# Master.net
KiCad netlist of a schematic drawn in Altium Designer
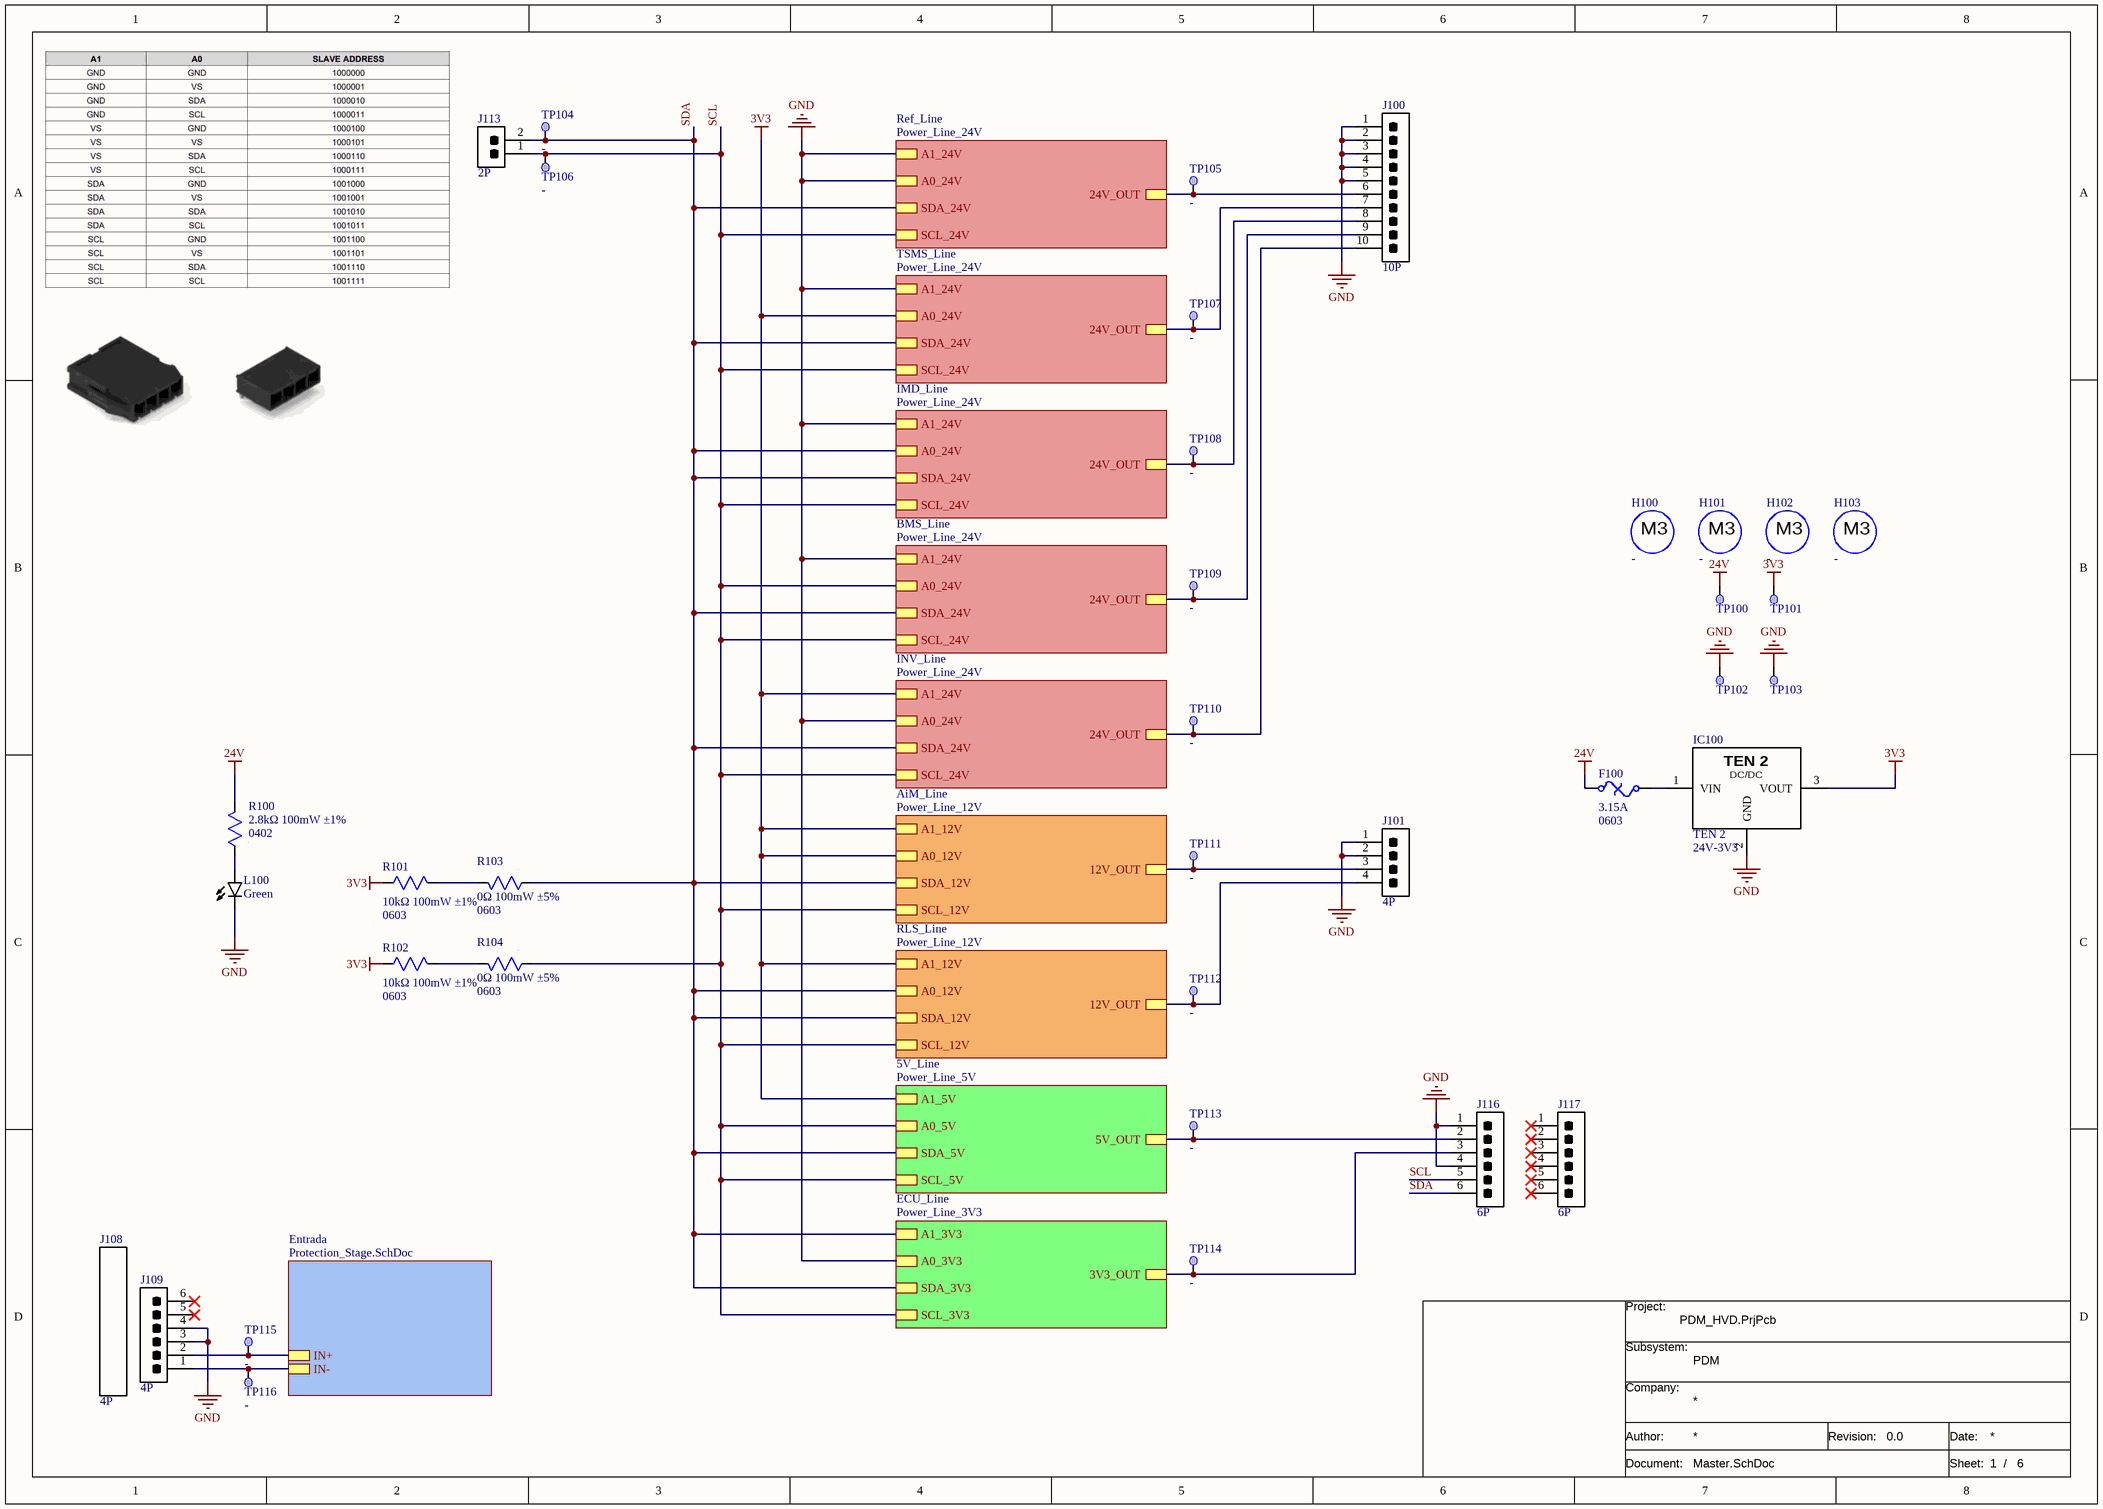
[diagram p0: Master.SchDoc]

(export (version "E")
  (design (tool "Eeschema 10.0.6"))
  (components
    (comp (ref "F100")
      (value "3.15A")
      (footprint "FUSE SMD 0603")
      (description "Surface Mount Fuses 3.15A Slow Blow 0603 SinglFuse")
      (fields
        (field (name "PACKAGE") "0603")
        (field (name "MPN") "SF-0603S315-2")
        (field (name "MANUFACTURER") "Bourns")
      )
      (libsource (lib "eUSR_Database") (part "FUSE"))
    )
    (comp (ref "H100")
      (value "-")
      (footprint "M3")
      (description "M3 Screw")
      (fields (field (name "Comment") "SCREW M3"))
      (libsource (lib "eUSR_Database") (part "SCREW M3"))
    )
    (comp (ref "H101")
      (value "-")
      (footprint "M3")
      (description "M3 Screw")
      (fields (field (name "Comment") "SCREW M3"))
      (libsource (lib "eUSR_Database") (part "SCREW M3"))
    )
    (comp (ref "H102")
      (value "-")
      (footprint "M3")
      (description "M3 Screw")
      (fields (field (name "Comment") "SCREW M3"))
      (libsource (lib "eUSR_Database") (part "SCREW M3"))
    )
    (comp (ref "H103")
      (value "-")
      (footprint "M3")
      (description "M3 Screw")
      (fields (field (name "Comment") "SCREW M3"))
      (libsource (lib "eUSR_Database") (part "SCREW M3"))
    )
    (comp (ref "IC100")
      (value "TEN 2")
      (footprint "TEN 2")
      (description "Convertidores DC/DC para montaje pasante 4.75-36Vin 3.3V 2A switching regulator")
      (fields
        (field (name "ALTIUM_VALUE") "24V-3V3")
        (field (name "MPN") "TSR 2-2433")
        (field (name "MANUFACTURER") "TRACO Power")
      )
      (libsource (lib "eUSR_Database") (part "TEN 2"))
    )
    (comp (ref "J100")
      (value "10P")
      (footprint "657010240101")
      (fields
        (field (name "MPN") "657010240101")
        (field (name "MANUFACTURER") "Wurth Elektronik")
        (field (name "Comment") "CONN 10P")
      )
      (libsource (lib "eUSR_Database") (part "CONN 10P"))
    )
    (comp (ref "J101")
      (value "4P")
      (footprint "657004240101")
      (fields
        (field (name "MPN") "657004240101")
        (field (name "MANUFACTURER") "Wurth Elektronik")
        (field (name "Comment") "CONN 4P")
      )
      (libsource (lib "eUSR_Database") (part "CONN 4P"))
    )
    (comp (ref "J108")
      (value "4P")
      (footprint "657004150201")
      (description "Receptacle Single Row")
      (fields (field (name "MPN") "657004150201") (field (name "MANUFACTURER") "Wurth Elektronik"))
      (libsource (lib "eUSR_Database") (part "AEREO"))
    )
    (comp (ref "J109")
      (value "4P")
      (footprint "657004140101")
      (description "WR-MPC5 Male Header Single Row")
      (fields (field (name "MPN") "657004140101") (field (name "MANUFACTURER") "Wurth Elektronik"))
      (libsource (lib "") (part "CONN 6P_1"))
    )
    (comp (ref "J113")
      (value "2P")
      (footprint "PIN_HEADER_THT_2P")
      (description "Alojamientos de cables y cabecera 2.54MM HIGH TEMP PCB HDR STRIP")
      (fields (field (name "MPN") "HTSW-102-07-G-S") (field (name "MANUFACTURER") "Samtec"))
      (libsource (lib "eUSR_Database") (part "CONN 2P"))
    )
    (comp (ref "J116")
      (value "6P")
      (footprint "HEADERS_MALE_6P_2.54MM")
      (description "Pin Header 6 Position 2.54mm Pitch Single Row Through Hole -55℃~+105℃")
      (fields (field (name "MPN") "2541WV-06P") (field (name "MANUFACTURER") "HanElectricity"))
      (libsource (lib "eUSR_Database") (part "CONN 6P"))
    )
    (comp (ref "J117")
      (value "6P")
      (footprint "HEADERS_MALE_6P_2.54MM")
      (description "Pin Header 6 Position 2.54mm Pitch Single Row Through Hole -55℃~+105℃")
      (fields (field (name "MPN") "2541WV-06P") (field (name "MANUFACTURER") "HanElectricity"))
      (libsource (lib "eUSR_Database") (part "CONN 6P"))
    )
    (comp (ref "L100")
      (value "Green")
      (footprint "LED SMD 0603")
      (description "LED de un solo color Green 525nm 1400mcd 2.85V 73deg 0603")
      (fields (field (name "MPN") "VLMTG1400-GS08") (field (name "MANUFACTURER") "Vishay Semiconductors"))
      (libsource (lib "eUSR_Database") (part "LED WHITE"))
    )
    (comp (ref "R100")
      (value "2.8kΩ 100mW ±1%")
      (footprint "RES SMD 0402")
      (description "Resistores de película gruesa - SMD WRIS-RSKS 28 kOhms 1 % 0.1 W 0402 AEC-Q200")
      (fields
        (field (name "PACKAGE") "0402")
        (field (name "MPN") "560112110228")
        (field (name "MANUFACTURER") "Wurth Elektronik")
      )
      (libsource (lib "eUSR_Database") (part "RES"))
    )
    (comp (ref "R101")
      (value "10kΩ 100mW ±1%")
      (footprint "RES SMD 0603")
      (description "Resistores de película gruesa - SMD WRIS-RSKS 10 kOhms 1 % 0.1 W 0603 AEC-Q200")
      (fields
        (field (name "PACKAGE") "0603")
        (field (name "MPN") "560112116005")
        (field (name "MANUFACTURER") "Wurth Elektronik")
      )
      (libsource (lib "eUSR_Database") (part "RES"))
    )
    (comp (ref "R102")
      (value "10kΩ 100mW ±1%")
      (footprint "RES SMD 0603")
      (description "Resistores de película gruesa - SMD WRIS-RSKS 10 kOhms 1 % 0.1 W 0603 AEC-Q200")
      (fields
        (field (name "PACKAGE") "0603")
        (field (name "MPN") "560112116005")
        (field (name "MANUFACTURER") "Wurth Elektronik")
      )
      (libsource (lib "eUSR_Database") (part "RES"))
    )
    (comp (ref "R103")
      (value "0Ω 100mW ±5%")
      (footprint "RES SMD 0603")
      (description "Resistores de película gruesa - SMD WRIS-RSKS <0.05 Ohms 0.1 W Jumper 0603 AEC-Q200")
      (fields
        (field (name "PACKAGE") "0603")
        (field (name "MPN") "560112116001")
        (field (name "MANUFACTURER") "Wurth Elektronik")
      )
      (libsource (lib "eUSR_Database") (part "RES"))
    )
    (comp (ref "R104")
      (value "0Ω 100mW ±5%")
      (footprint "RES SMD 0603")
      (description "Resistores de película gruesa - SMD WRIS-RSKS <0.05 Ohms 0.1 W Jumper 0603 AEC-Q200")
      (fields
        (field (name "PACKAGE") "0603")
        (field (name "MPN") "560112116001")
        (field (name "MANUFACTURER") "Wurth Elektronik")
      )
      (libsource (lib "eUSR_Database") (part "RES"))
    )
    (comp (ref "TP100")
      (value "Test Point")
      (footprint "TP_THT_1.5MM")
      (description "Test Point 1.5mm THT")
      (libsource (lib "eUSR_Database") (part "TP"))
    )
    (comp (ref "TP101")
      (value "Test Point")
      (footprint "TP_THT_1.5MM")
      (description "Test Point 1.5mm THT")
      (libsource (lib "eUSR_Database") (part "TP"))
    )
    (comp (ref "TP102")
      (value "Test Point")
      (footprint "TP_THT_1.5MM")
      (description "Test Point 1.5mm THT")
      (libsource (lib "eUSR_Database") (part "TP"))
    )
    (comp (ref "TP103")
      (value "Test Point")
      (footprint "TP_THT_1.5MM")
      (description "Test Point 1.5mm THT")
      (libsource (lib "eUSR_Database") (part "TP"))
    )
    (comp (ref "TP104")
      (value "-")
      (footprint "TP_SMD_1MM")
      (description "Test Point")
      (libsource (lib "eUSR_Database") (part "TP1mm"))
    )
    (comp (ref "TP105")
      (value "-")
      (footprint "TP_SMD_1MM")
      (description "Test Point")
      (libsource (lib "eUSR_Database") (part "TP1mm"))
    )
    (comp (ref "TP106")
      (value "-")
      (footprint "TP_SMD_1MM")
      (description "Test Point")
      (libsource (lib "") (part "TP1mm_1"))
    )
    (comp (ref "TP107")
      (value "-")
      (footprint "TP_SMD_1MM")
      (description "Test Point")
      (libsource (lib "eUSR_Database") (part "TP1mm"))
    )
    (comp (ref "TP108")
      (value "-")
      (footprint "TP_SMD_1MM")
      (description "Test Point")
      (libsource (lib "eUSR_Database") (part "TP1mm"))
    )
    (comp (ref "TP109")
      (value "-")
      (footprint "TP_SMD_1MM")
      (description "Test Point")
      (libsource (lib "eUSR_Database") (part "TP1mm"))
    )
    (comp (ref "TP110")
      (value "-")
      (footprint "TP_SMD_1MM")
      (description "Test Point")
      (libsource (lib "eUSR_Database") (part "TP1mm"))
    )
    (comp (ref "TP111")
      (value "-")
      (footprint "TP_SMD_1MM")
      (description "Test Point")
      (libsource (lib "eUSR_Database") (part "TP1mm"))
    )
    (comp (ref "TP112")
      (value "-")
      (footprint "TP_SMD_1MM")
      (description "Test Point")
      (libsource (lib "eUSR_Database") (part "TP1mm"))
    )
    (comp (ref "TP113")
      (value "-")
      (footprint "TP_SMD_1MM")
      (description "Test Point")
      (libsource (lib "eUSR_Database") (part "TP1mm"))
    )
    (comp (ref "TP114")
      (value "-")
      (footprint "TP_SMD_1MM")
      (description "Test Point")
      (libsource (lib "eUSR_Database") (part "TP1mm"))
    )
    (comp (ref "TP115")
      (value "-")
      (footprint "TP_SMD_1MM")
      (description "Test Point")
      (libsource (lib "eUSR_Database") (part "TP1mm"))
    )
    (comp (ref "TP116")
      (value "-")
      (footprint "TP_SMD_1MM")
      (description "Test Point")
      (libsource (lib "") (part "TP1mm_1"))
    )
  )
  (nets
    (net (code "1") (name "/3V3_OUT") (class "Default")
      (node (ref "J116") (pin "3") (pinfunction "3_3") (pintype "passive"))
      (node (ref "TP114") (pin "1") (pinfunction "1_1") (pintype "passive"))
    )
    (net (code "2") (name "/5V_OUT") (class "Default")
      (node (ref "J116") (pin "2") (pinfunction "2_2") (pintype "passive"))
      (node (ref "TP113") (pin "1") (pinfunction "1_1") (pintype "passive"))
    )
    (net (code "3") (name "/12V_OUT") (class "Default")
      (node (ref "J101") (pin "4") (pinfunction "4_4") (pintype "passive"))
      (node (ref "TP112") (pin "1") (pinfunction "1_1") (pintype "passive"))
    )
    (net (code "4") (name "/12V_OUT_1") (class "Default")
      (node (ref "J101") (pin "3") (pinfunction "3_3") (pintype "passive"))
      (node (ref "TP111") (pin "1") (pinfunction "1_1") (pintype "passive"))
    )
    (net (code "5") (name "/24V_OUT") (class "Default")
      (node (ref "J100") (pin "10") (pinfunction "10_10") (pintype "passive"))
      (node (ref "TP110") (pin "1") (pinfunction "1_1") (pintype "passive"))
    )
    (net (code "6") (name "/24V_OUT_1") (class "Default")
      (node (ref "J100") (pin "6") (pinfunction "6_6") (pintype "passive"))
      (node (ref "TP105") (pin "1") (pinfunction "1_1") (pintype "passive"))
    )
    (net (code "7") (name "/24V_OUT_2") (class "Default")
      (node (ref "J100") (pin "7") (pinfunction "7_7") (pintype "passive"))
      (node (ref "TP107") (pin "1") (pinfunction "1_1") (pintype "passive"))
    )
    (net (code "8") (name "/24V_OUT_3") (class "Default")
      (node (ref "J100") (pin "8") (pinfunction "8_8") (pintype "passive"))
      (node (ref "TP108") (pin "1") (pinfunction "1_1") (pintype "passive"))
    )
    (net (code "9") (name "/24V_OUT_4") (class "Default")
      (node (ref "J100") (pin "9") (pinfunction "9_9") (pintype "passive"))
      (node (ref "TP109") (pin "1") (pinfunction "1_1") (pintype "passive"))
    )
    (net (code "10") (name "/IN+") (class "Default")
      (node (ref "J109") (pin "2") (pinfunction "2_2") (pintype "passive"))
      (node (ref "TP115") (pin "1") (pinfunction "1_1") (pintype "passive"))
    )
    (net (code "11") (name "/IN-") (class "Default")
      (node (ref "J109") (pin "1") (pinfunction "1_1") (pintype "passive"))
      (node (ref "TP116") (pin "1") (pinfunction "1_1") (pintype "passive"))
    )
    (net (code "12") (name "/SCL") (class "Default")
      (node (ref "J113") (pin "1") (pinfunction "1_1") (pintype "passive"))
      (node (ref "J116") (pin "5") (pinfunction "5_5") (pintype "passive"))
      (node (ref "R104") (pin "1") (pinfunction "1_1") (pintype "passive"))
      (node (ref "TP106") (pin "1") (pinfunction "1_1") (pintype "passive"))
    )
    (net (code "13") (name "/SDA") (class "Default")
      (node (ref "J113") (pin "2") (pinfunction "2_2") (pintype "passive"))
      (node (ref "J116") (pin "6") (pinfunction "6_6") (pintype "passive"))
      (node (ref "R103") (pin "1") (pinfunction "1_1") (pintype "passive"))
      (node (ref "TP104") (pin "1") (pinfunction "1_1") (pintype "passive"))
    )
    (net (code "14") (name "3V3") (class "Default")
      (node (ref "IC100") (pin "3") (pinfunction "VOUT_3") (pintype "passive"))
      (node (ref "R101") (pin "1") (pinfunction "1_1") (pintype "passive"))
      (node (ref "R102") (pin "1") (pinfunction "1_1") (pintype "passive"))
      (node (ref "TP101") (pin "1") (pinfunction "1_1") (pintype "passive"))
    )
    (net (code "15") (name "24V") (class "Default")
      (node (ref "F100") (pin "1") (pinfunction "1_1") (pintype "passive"))
      (node (ref "R100") (pin "2") (pinfunction "2_2") (pintype "passive"))
      (node (ref "TP100") (pin "1") (pinfunction "1_1") (pintype "passive"))
    )
    (net (code "16") (name "GND") (class "Default")
      (node (ref "IC100") (pin "2") (pinfunction "GND_2") (pintype "passive"))
      (node (ref "J100") (pin "1") (pinfunction "1_1") (pintype "passive"))
      (node (ref "J100") (pin "2") (pinfunction "2_2") (pintype "passive"))
      (node (ref "J100") (pin "3") (pinfunction "3_3") (pintype "passive"))
      (node (ref "J100") (pin "4") (pinfunction "4_4") (pintype "passive"))
      (node (ref "J100") (pin "5") (pinfunction "5_5") (pintype "passive"))
      (node (ref "J101") (pin "1") (pinfunction "1_1") (pintype "passive"))
      (node (ref "J101") (pin "2") (pinfunction "2_2") (pintype "passive"))
      (node (ref "J109") (pin "3") (pinfunction "3_3") (pintype "passive"))
      (node (ref "J109") (pin "4") (pinfunction "4_4") (pintype "passive"))
      (node (ref "J116") (pin "1") (pinfunction "1_1") (pintype "passive"))
      (node (ref "J116") (pin "4") (pinfunction "4_4") (pintype "passive"))
      (node (ref "L100") (pin "C") (pinfunction "C_C") (pintype "passive"))
      (node (ref "TP102") (pin "1") (pinfunction "1_1") (pintype "passive"))
      (node (ref "TP103") (pin "1") (pinfunction "1_1") (pintype "passive"))
    )
    (net (code "17") (name "Net-(IC100-VIN)") (class "Default")
      (node (ref "F100") (pin "2") (pinfunction "2_2") (pintype "passive"))
      (node (ref "IC100") (pin "1") (pinfunction "VIN_1") (pintype "passive"))
    )
    (net (code "18") (name "Net-(L100-PadA)") (class "Default")
      (node (ref "L100") (pin "A") (pinfunction "A_A") (pintype "passive"))
      (node (ref "R100") (pin "1") (pinfunction "1_1") (pintype "passive"))
    )
    (net (code "19") (name "Net-(R101-Pad2)") (class "Default")
      (node (ref "R101") (pin "2") (pinfunction "2_2") (pintype "passive"))
      (node (ref "R103") (pin "2") (pinfunction "2_2") (pintype "passive"))
    )
    (net (code "20") (name "Net-(R102-Pad2)") (class "Default")
      (node (ref "R102") (pin "2") (pinfunction "2_2") (pintype "passive"))
      (node (ref "R104") (pin "2") (pinfunction "2_2") (pintype "passive"))
    )
    (net (code "21") (name "unconnected-(J109-Pad5)") (class "Default")
      (node (ref "J109") (pin "5") (pinfunction "5_5") (pintype "passive+no_connect"))
    )
    (net (code "22") (name "unconnected-(J109-Pad6)") (class "Default")
      (node (ref "J109") (pin "6") (pinfunction "6_6") (pintype "passive+no_connect"))
    )
    (net (code "23") (name "unconnected-(J117-Pad1)") (class "Default")
      (node (ref "J117") (pin "1") (pinfunction "1_1") (pintype "passive+no_connect"))
    )
    (net (code "24") (name "unconnected-(J117-Pad2)") (class "Default")
      (node (ref "J117") (pin "2") (pinfunction "2_2") (pintype "passive+no_connect"))
    )
    (net (code "25") (name "unconnected-(J117-Pad3)") (class "Default")
      (node (ref "J117") (pin "3") (pinfunction "3_3") (pintype "passive+no_connect"))
    )
    (net (code "26") (name "unconnected-(J117-Pad4)") (class "Default")
      (node (ref "J117") (pin "4") (pinfunction "4_4") (pintype "passive+no_connect"))
    )
    (net (code "27") (name "unconnected-(J117-Pad5)") (class "Default")
      (node (ref "J117") (pin "5") (pinfunction "5_5") (pintype "passive+no_connect"))
    )
    (net (code "28") (name "unconnected-(J117-Pad6)") (class "Default")
      (node (ref "J117") (pin "6") (pinfunction "6_6") (pintype "passive+no_connect"))
    )
  )
)
